# heliograph.net
KiCad netlist of a schematic drawn in EAGLE
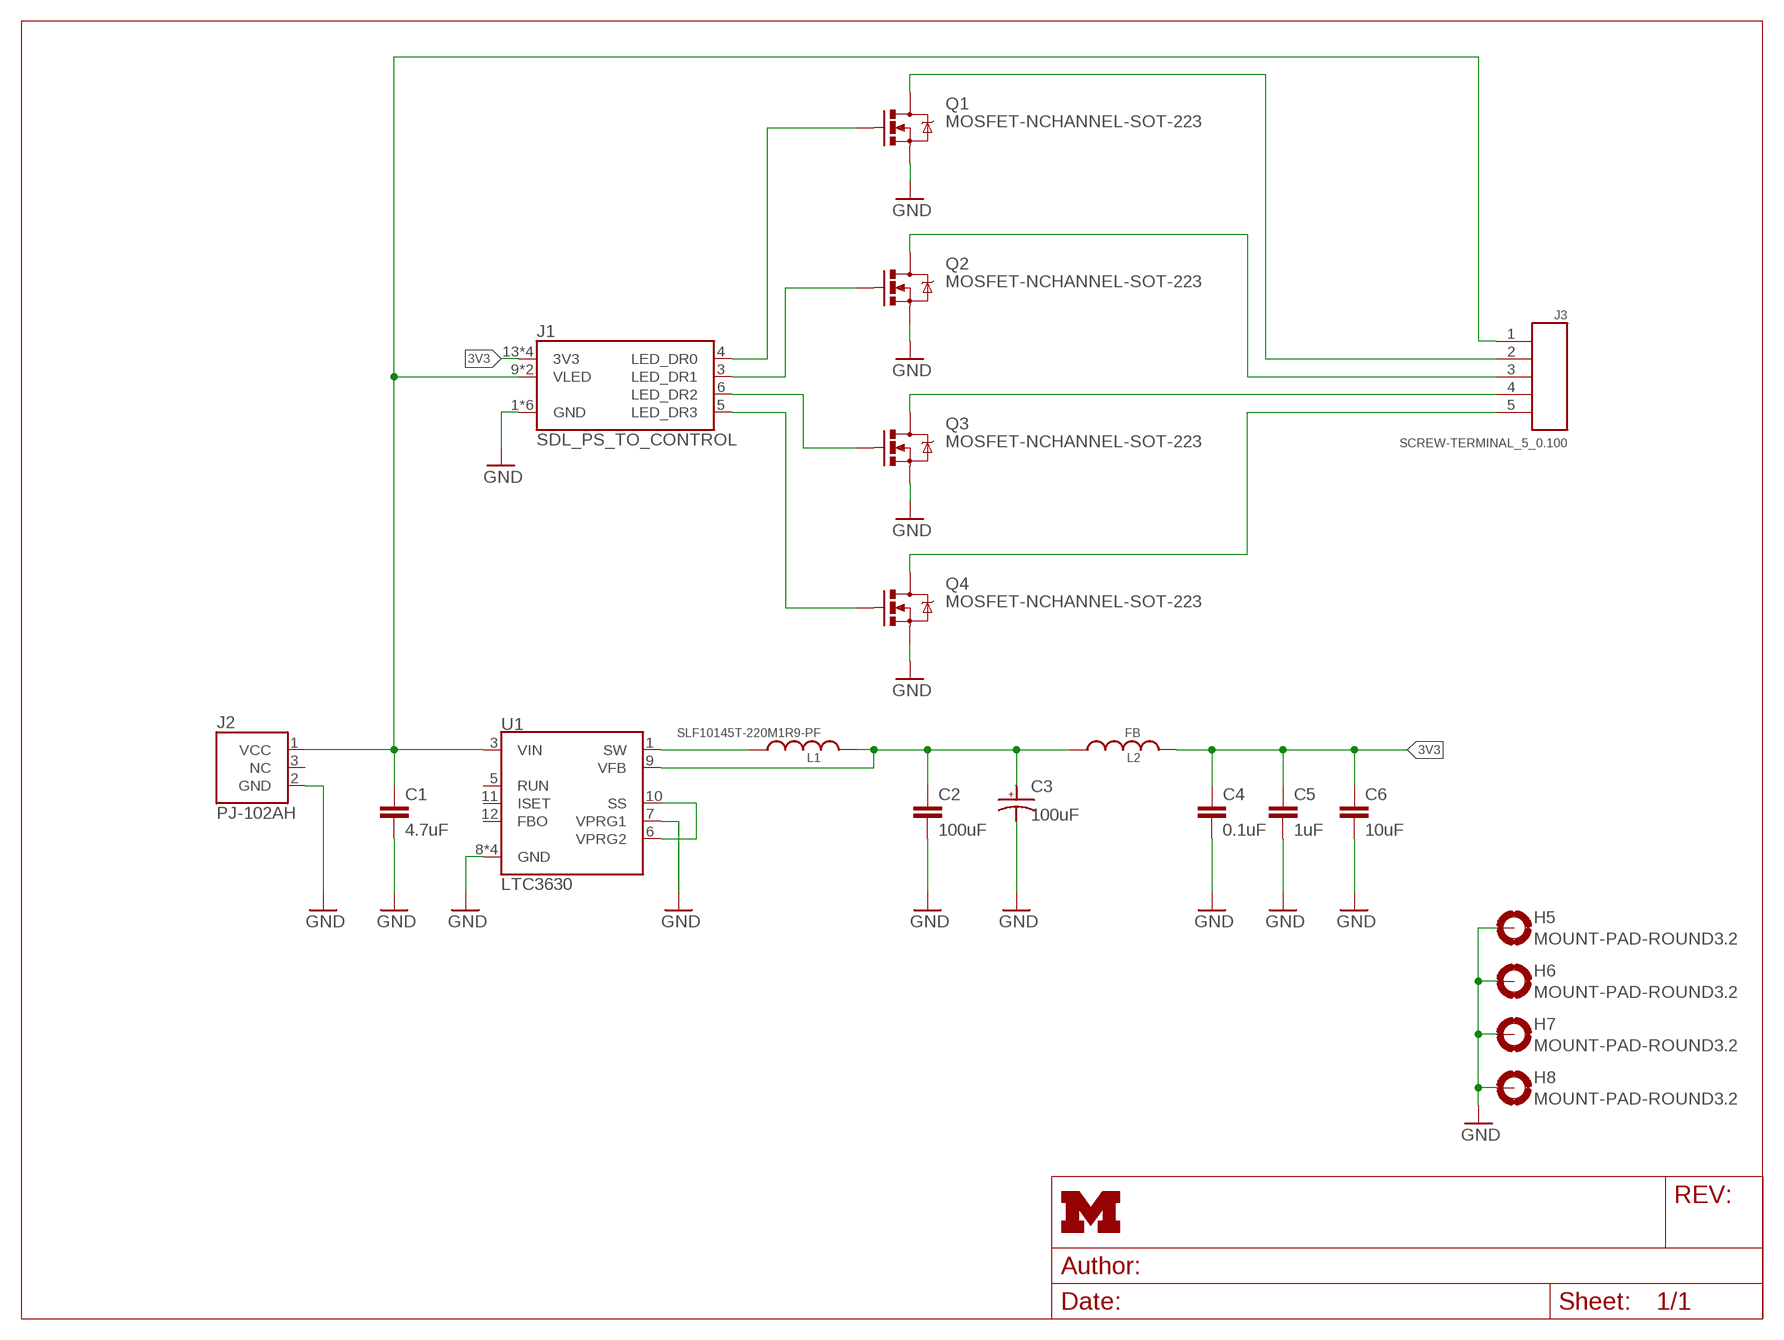
[diagram p0: schematic, sheet 1]

(export (version "E")
  (design (tool "Eeschema 10.0.6"))
  (components
    (comp (ref "C1")
      (value "4.7uF")
      (footprint "eagle-import:C2220K")
      (libsource (lib "eagle-import") (part "C-EUC2220K"))
    )
    (comp (ref "C2")
      (value "100uF")
      (footprint "eagle-import:C1210")
      (libsource (lib "eagle-import") (part "C-EUC1210"))
    )
    (comp (ref "C3")
      (value "100uF")
      (footprint "eagle-import:2917-POL")
      (libsource (lib "eagle-import") (part "CAP_POL2917"))
    )
    (comp (ref "C4")
      (value "0.1uF")
      (footprint "eagle-import:C0603")
      (libsource (lib "eagle-import") (part "C-EUC0603"))
    )
    (comp (ref "C5")
      (value "1uF")
      (footprint "eagle-import:C0603")
      (libsource (lib "eagle-import") (part "C-EUC0603"))
    )
    (comp (ref "C6")
      (value "10uF")
      (footprint "eagle-import:C0603")
      (libsource (lib "eagle-import") (part "C-EUC0603"))
    )
    (comp (ref "H5")
      (value "MOUNT-PAD-ROUND3.2")
      (footprint "eagle-import:3,2-PAD")
      (libsource (lib "eagle-import") (part "MOUNT-PAD-ROUND3.2"))
    )
    (comp (ref "H6")
      (value "MOUNT-PAD-ROUND3.2")
      (footprint "eagle-import:3,2-PAD")
      (libsource (lib "eagle-import") (part "MOUNT-PAD-ROUND3.2"))
    )
    (comp (ref "H7")
      (value "MOUNT-PAD-ROUND3.2")
      (footprint "eagle-import:3,2-PAD")
      (libsource (lib "eagle-import") (part "MOUNT-PAD-ROUND3.2"))
    )
    (comp (ref "H8")
      (value "MOUNT-PAD-ROUND3.2")
      (footprint "eagle-import:3,2-PAD")
      (libsource (lib "eagle-import") (part "MOUNT-PAD-ROUND3.2"))
    )
    (comp (ref "J1")
      (value "SDL_PS_TO_CONTROL")
      (footprint "eagle-import:SDL_PS_TO_CONTROL")
      (libsource (lib "eagle-import") (part "SDL_PS_TO_CONTROL"))
    )
    (comp (ref "J2")
      (value "PJ-102AH")
      (footprint "eagle-import:PJ-102AH")
      (libsource (lib "eagle-import") (part "PJ-102AH"))
    )
    (comp (ref "J3")
      (value "SCREW-TERMINAL_5_0.100")
      (footprint "eagle-import:CONN_BLOCK_5")
      (libsource (lib "eagle-import") (part "SCREW-TERMINAL_5_0.100"))
    )
    (comp (ref "L1")
      (value "SLF10145T-220M1R9-PF")
      (footprint "eagle-import:SLF10145")
      (libsource (lib "eagle-import") (part "SLF10145T-220M1R9-PF"))
    )
    (comp (ref "L2")
      (value "FB")
      (footprint "eagle-import:0603_CAP")
      (libsource (lib "eagle-import") (part "INDUCTOR0603"))
    )
    (comp (ref "Q1")
      (value "MOSFET-NCHANNEL-SOT-223")
      (footprint "eagle-import:SOT-223")
      (libsource (lib "eagle-import") (part "MOSFET-NCHANNEL-SOT-223"))
    )
    (comp (ref "Q2")
      (value "MOSFET-NCHANNEL-SOT-223")
      (footprint "eagle-import:SOT-223")
      (libsource (lib "eagle-import") (part "MOSFET-NCHANNEL-SOT-223"))
    )
    (comp (ref "Q3")
      (value "MOSFET-NCHANNEL-SOT-223")
      (footprint "eagle-import:SOT-223")
      (libsource (lib "eagle-import") (part "MOSFET-NCHANNEL-SOT-223"))
    )
    (comp (ref "Q4")
      (value "MOSFET-NCHANNEL-SOT-223")
      (footprint "eagle-import:SOT-223")
      (libsource (lib "eagle-import") (part "MOSFET-NCHANNEL-SOT-223"))
    )
    (comp (ref "U1")
      (value "LTC3630")
      (footprint "eagle-import:MSOP-16(12)")
      (libsource (lib "eagle-import") (part "LTC3630"))
    )
  )
  (nets
    (net (code "1") (name "3V3") (class "Default")
      (node (ref "C4") (pin "1") (pinfunction "1_1") (pintype "passive"))
      (node (ref "C5") (pin "1") (pinfunction "1_1") (pintype "passive"))
      (node (ref "C6") (pin "1") (pinfunction "1_1") (pintype "passive"))
      (node (ref "J1") (pin "13") (pinfunction "3V3_13") (pintype "bidirectional"))
      (node (ref "J1") (pin "14") (pinfunction "3V3_14") (pintype "bidirectional"))
      (node (ref "J1") (pin "15") (pinfunction "3V3_15") (pintype "bidirectional"))
      (node (ref "J1") (pin "16") (pinfunction "3V3_16") (pintype "bidirectional"))
      (node (ref "L2") (pin "2") (pinfunction "2_2") (pintype "bidirectional"))
    )
    (net (code "2") (name "GND") (class "Default")
      (node (ref "C1") (pin "2") (pinfunction "2_2") (pintype "passive"))
      (node (ref "C2") (pin "2") (pinfunction "2_2") (pintype "passive"))
      (node (ref "C3") (pin "-") (pinfunction "ANODE_-") (pintype "bidirectional"))
      (node (ref "C4") (pin "2") (pinfunction "2_2") (pintype "passive"))
      (node (ref "C5") (pin "2") (pinfunction "2_2") (pintype "passive"))
      (node (ref "C6") (pin "2") (pinfunction "2_2") (pintype "passive"))
      (node (ref "H5") (pin "B3,2") (pinfunction "MOUNT_B3,2") (pintype "passive"))
      (node (ref "H6") (pin "B3,2") (pinfunction "MOUNT_B3,2") (pintype "passive"))
      (node (ref "H7") (pin "B3,2") (pinfunction "MOUNT_B3,2") (pintype "passive"))
      (node (ref "H8") (pin "B3,2") (pinfunction "MOUNT_B3,2") (pintype "passive"))
      (node (ref "J1") (pin "1") (pinfunction "GND_1") (pintype "bidirectional"))
      (node (ref "J1") (pin "11") (pinfunction "GND_11") (pintype "bidirectional"))
      (node (ref "J1") (pin "12") (pinfunction "GND_12") (pintype "bidirectional"))
      (node (ref "J1") (pin "2") (pinfunction "GND_2") (pintype "bidirectional"))
      (node (ref "J1") (pin "7") (pinfunction "GND_7") (pintype "bidirectional"))
      (node (ref "J1") (pin "8") (pinfunction "GND_8") (pintype "bidirectional"))
      (node (ref "J2") (pin "2") (pinfunction "GND_2") (pintype "bidirectional"))
      (node (ref "Q1") (pin "3") (pinfunction "S_3") (pintype "passive"))
      (node (ref "Q2") (pin "3") (pinfunction "S_3") (pintype "passive"))
      (node (ref "Q3") (pin "3") (pinfunction "S_3") (pintype "passive"))
      (node (ref "Q4") (pin "3") (pinfunction "S_3") (pintype "passive"))
      (node (ref "U1") (pin "14") (pinfunction "GND_14") (pintype "bidirectional"))
      (node (ref "U1") (pin "16") (pinfunction "GND_16") (pintype "bidirectional"))
      (node (ref "U1") (pin "17") (pinfunction "GND_17") (pintype "bidirectional"))
      (node (ref "U1") (pin "7") (pinfunction "VPRG1_7") (pintype "bidirectional"))
      (node (ref "U1") (pin "8") (pinfunction "GND_8") (pintype "bidirectional"))
    )
    (net (code "3") (name "Net-(C3-CATHODE)") (class "Default")
      (node (ref "C2") (pin "1") (pinfunction "1_1") (pintype "passive"))
      (node (ref "C3") (pin "+") (pinfunction "CATHODE_+") (pintype "bidirectional"))
      (node (ref "L1") (pin "2") (pinfunction "2_2") (pintype "bidirectional"))
      (node (ref "L2") (pin "1") (pinfunction "1_1") (pintype "bidirectional"))
      (node (ref "U1") (pin "9") (pinfunction "VFB_9") (pintype "bidirectional"))
    )
    (net (code "4") (name "Net-(J1-LED_DR0)") (class "Default")
      (node (ref "J1") (pin "4") (pinfunction "LED_DR0_4") (pintype "bidirectional"))
      (node (ref "Q1") (pin "1") (pinfunction "G_1") (pintype "passive"))
    )
    (net (code "5") (name "Net-(J1-LED_DR1)") (class "Default")
      (node (ref "J1") (pin "3") (pinfunction "LED_DR1_3") (pintype "bidirectional"))
      (node (ref "Q2") (pin "1") (pinfunction "G_1") (pintype "passive"))
    )
    (net (code "6") (name "Net-(J1-LED_DR2)") (class "Default")
      (node (ref "J1") (pin "6") (pinfunction "LED_DR2_6") (pintype "bidirectional"))
      (node (ref "Q3") (pin "1") (pinfunction "G_1") (pintype "passive"))
    )
    (net (code "7") (name "Net-(J1-LED_DR3)") (class "Default")
      (node (ref "J1") (pin "5") (pinfunction "LED_DR3_5") (pintype "bidirectional"))
      (node (ref "Q4") (pin "1") (pinfunction "G_1") (pintype "passive"))
    )
    (net (code "8") (name "Net-(J2-VCC)") (class "Default")
      (node (ref "C1") (pin "1") (pinfunction "1_1") (pintype "passive"))
      (node (ref "J1") (pin "10") (pinfunction "VLED_10") (pintype "bidirectional"))
      (node (ref "J1") (pin "9") (pinfunction "VLED_9") (pintype "bidirectional"))
      (node (ref "J2") (pin "1") (pinfunction "VCC_1") (pintype "bidirectional"))
      (node (ref "J3") (pin "1") (pinfunction "1_1") (pintype "bidirectional"))
      (node (ref "U1") (pin "3") (pinfunction "VIN_3") (pintype "bidirectional"))
    )
    (net (code "9") (name "Net-(J3-Pad2)") (class "Default")
      (node (ref "J3") (pin "2") (pinfunction "2_2") (pintype "bidirectional"))
      (node (ref "Q1") (pin "2") (pinfunction "D_2") (pintype "passive"))
      (node (ref "Q1") (pin "4") (pinfunction "D_4") (pintype "passive"))
    )
    (net (code "10") (name "Net-(J3-Pad3)") (class "Default")
      (node (ref "J3") (pin "3") (pinfunction "3_3") (pintype "bidirectional"))
      (node (ref "Q2") (pin "2") (pinfunction "D_2") (pintype "passive"))
      (node (ref "Q2") (pin "4") (pinfunction "D_4") (pintype "passive"))
    )
    (net (code "11") (name "Net-(J3-Pad4)") (class "Default")
      (node (ref "J3") (pin "4") (pinfunction "4_4") (pintype "bidirectional"))
      (node (ref "Q3") (pin "2") (pinfunction "D_2") (pintype "passive"))
      (node (ref "Q3") (pin "4") (pinfunction "D_4") (pintype "passive"))
    )
    (net (code "12") (name "Net-(J3-Pad5)") (class "Default")
      (node (ref "J3") (pin "5") (pinfunction "5_5") (pintype "bidirectional"))
      (node (ref "Q4") (pin "2") (pinfunction "D_2") (pintype "passive"))
      (node (ref "Q4") (pin "4") (pinfunction "D_4") (pintype "passive"))
    )
    (net (code "13") (name "Net-(U1-SS)") (class "Default")
      (node (ref "U1") (pin "10") (pinfunction "SS_10") (pintype "bidirectional"))
      (node (ref "U1") (pin "6") (pinfunction "VPRG2_6") (pintype "bidirectional"))
    )
    (net (code "14") (name "Net-(U1-SW)") (class "Default")
      (node (ref "L1") (pin "1") (pinfunction "1_1") (pintype "bidirectional"))
      (node (ref "U1") (pin "1") (pinfunction "SW_1") (pintype "bidirectional"))
    )
    (net (code "15") (name "unconnected-(J2-NC-Pad3)") (class "Default")
      (node (ref "J2") (pin "3") (pinfunction "NC_3") (pintype "bidirectional"))
    )
    (net (code "16") (name "unconnected-(U1-FBO-Pad12)") (class "Default")
      (node (ref "U1") (pin "12") (pinfunction "FBO_12") (pintype "bidirectional"))
    )
    (net (code "17") (name "unconnected-(U1-ISET-Pad11)") (class "Default")
      (node (ref "U1") (pin "11") (pinfunction "ISET_11") (pintype "bidirectional"))
    )
    (net (code "18") (name "unconnected-(U1-RUN-Pad5)") (class "Default")
      (node (ref "U1") (pin "5") (pinfunction "RUN_5") (pintype "bidirectional"))
    )
  )
)
